# Moof_Janibore.net
KiCad netlist of a schematic drawn in EAGLE
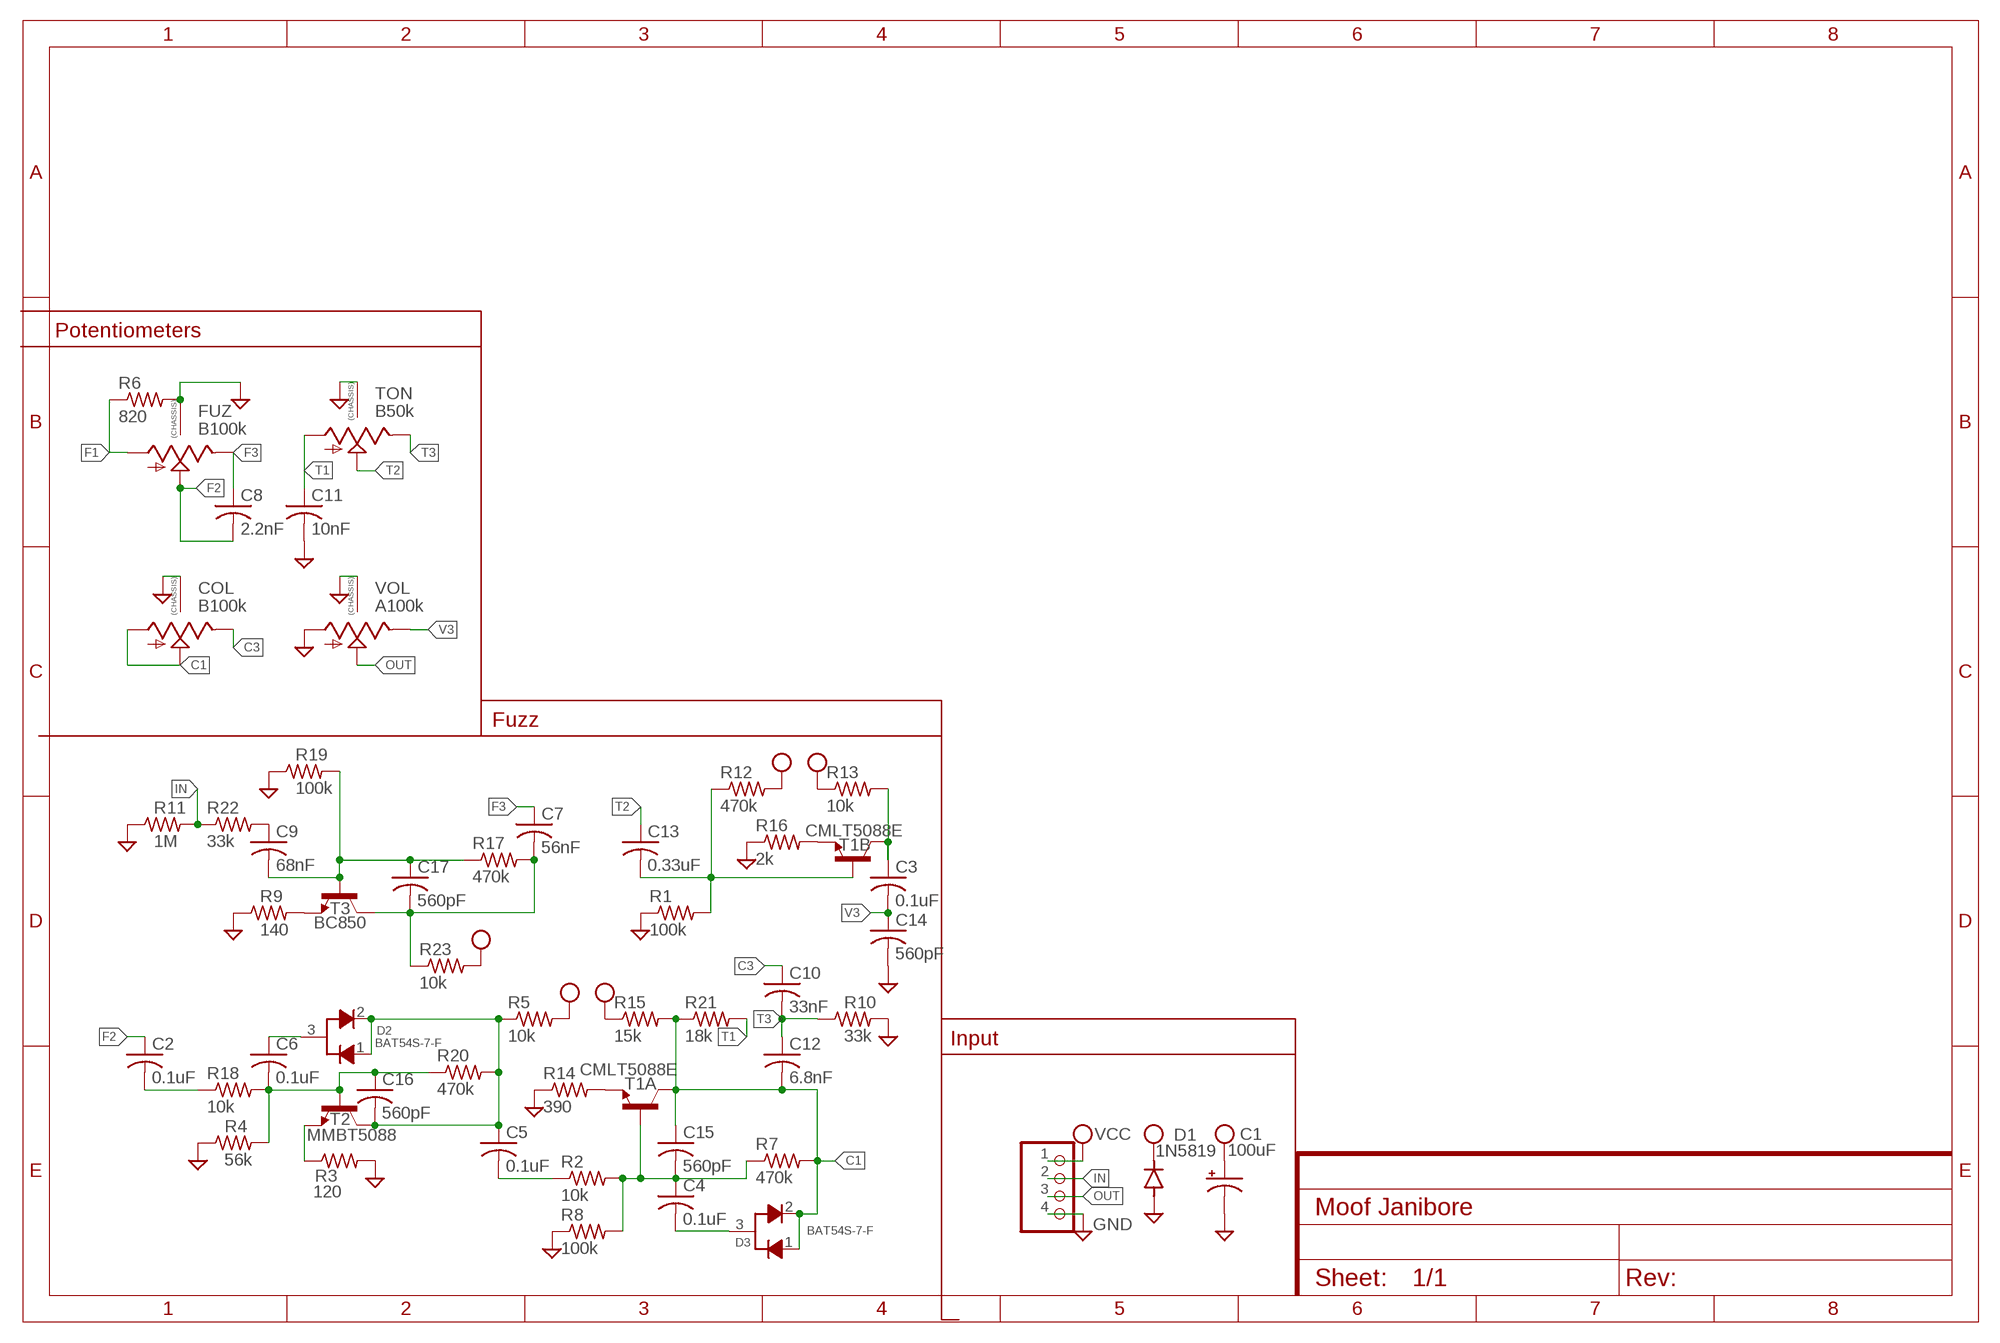
[diagram p0: schematic, sheet 1]

(export (version "E")
  (design (tool "Eeschema 10.0.6"))
  (components
    (comp (ref "C1")
      (value "100uF")
      (footprint "eagle-import:PAN_B_SMD+THRU")
      (libsource (lib "eagle-import") (part "CAP_SMD+THRUPAN_B"))
    )
    (comp (ref "C2")
      (value "0.1uF")
      (footprint "eagle-import:C0402")
      (libsource (lib "eagle-import") (part "C-USC0402"))
    )
    (comp (ref "C3")
      (value "0.1uF")
      (footprint "eagle-import:C0402")
      (libsource (lib "eagle-import") (part "C-USC0402"))
    )
    (comp (ref "C4")
      (value "0.1uF")
      (footprint "eagle-import:C0402")
      (libsource (lib "eagle-import") (part "C-USC0402"))
    )
    (comp (ref "C5")
      (value "0.1uF")
      (footprint "eagle-import:C0402")
      (libsource (lib "eagle-import") (part "C-USC0402"))
    )
    (comp (ref "C6")
      (value "0.1uF")
      (footprint "eagle-import:C0402")
      (libsource (lib "eagle-import") (part "C-USC0402"))
    )
    (comp (ref "C7")
      (value "56nF")
      (footprint "eagle-import:C0402")
      (libsource (lib "eagle-import") (part "C-USC0402"))
    )
    (comp (ref "C8")
      (value "2.2nF")
      (footprint "eagle-import:C0402")
      (libsource (lib "eagle-import") (part "C-USC0402"))
    )
    (comp (ref "C9")
      (value "68nF")
      (footprint "eagle-import:C0402")
      (libsource (lib "eagle-import") (part "C-USC0402"))
    )
    (comp (ref "C10")
      (value "33nF")
      (footprint "eagle-import:C0402")
      (libsource (lib "eagle-import") (part "C-USC0402"))
    )
    (comp (ref "C11")
      (value "10nF")
      (footprint "eagle-import:C0402")
      (libsource (lib "eagle-import") (part "C-USC0402"))
    )
    (comp (ref "C12")
      (value "6.8nF")
      (footprint "eagle-import:C0402")
      (libsource (lib "eagle-import") (part "C-USC0402"))
    )
    (comp (ref "C13")
      (value "0.33uF")
      (footprint "eagle-import:C0402")
      (libsource (lib "eagle-import") (part "C-USC0402"))
    )
    (comp (ref "C14")
      (value "560pF")
      (footprint "eagle-import:C0402")
      (libsource (lib "eagle-import") (part "C-USC0402"))
    )
    (comp (ref "C15")
      (value "560pF")
      (footprint "eagle-import:C0402")
      (libsource (lib "eagle-import") (part "C-USC0402"))
    )
    (comp (ref "C16")
      (value "560pF")
      (footprint "eagle-import:C0402")
      (libsource (lib "eagle-import") (part "C-USC0402"))
    )
    (comp (ref "C17")
      (value "560pF")
      (footprint "eagle-import:C0402")
      (libsource (lib "eagle-import") (part "C-USC0402"))
    )
    (comp (ref "COL")
      (value "B100k")
      (footprint "eagle-import:9MM_SNAP-IN_POT")
      (libsource (lib "eagle-import") (part "9MM_SNAP-IN_POT_CHASSIS"))
    )
    (comp (ref "D1")
      (value "1N5819")
      (footprint "eagle-import:SOD123")
      (libsource (lib "eagle-import") (part "DIODE-SOD123"))
    )
    (comp (ref "D2")
      (value "BAT54S-7-F")
      (footprint "eagle-import:SOT23-3")
      (fields
        (field (name "DIGIKEY_PART_NUMBER") "BAT54S-FDITR-ND")
        (field (name "MANUFACTURER") "Diodes Incorporated")
        (field (name "CREATED_BY") "PCBLayout.com")
      )
      (libsource (lib "eagle-import") (part "BAT54S-7-F"))
    )
    (comp (ref "D3")
      (value "BAT54S-7-F")
      (footprint "eagle-import:SOT23-3")
      (fields
        (field (name "DIGIKEY_PART_NUMBER") "BAT54S-FDITR-ND")
        (field (name "MANUFACTURER") "Diodes Incorporated")
        (field (name "CREATED_BY") "PCBLayout.com")
      )
      (libsource (lib "eagle-import") (part "BAT54S-7-F"))
    )
    (comp (ref "FUZ")
      (value "B100k")
      (footprint "eagle-import:9MM_SNAP-IN_POT")
      (libsource (lib "eagle-import") (part "9MM_SNAP-IN_POT_CHASSIS"))
    )
    (comp (ref "JP1")
      (value "PINHD-1X4")
      (footprint "eagle-import:1X04")
      (libsource (lib "eagle-import") (part "PINHD-1X4"))
    )
    (comp (ref "R1")
      (value "100k")
      (footprint "eagle-import:R0402")
      (libsource (lib "eagle-import") (part "R-US_R0402"))
    )
    (comp (ref "R2")
      (value "10k")
      (footprint "eagle-import:R0402")
      (libsource (lib "eagle-import") (part "R-US_R0402"))
    )
    (comp (ref "R3")
      (value "120")
      (footprint "eagle-import:R0402")
      (libsource (lib "eagle-import") (part "R-US_R0402"))
    )
    (comp (ref "R4")
      (value "56k")
      (footprint "eagle-import:R0402")
      (libsource (lib "eagle-import") (part "R-US_R0402"))
    )
    (comp (ref "R5")
      (value "10k")
      (footprint "eagle-import:R0402")
      (libsource (lib "eagle-import") (part "R-US_R0402"))
    )
    (comp (ref "R6")
      (value "820")
      (footprint "eagle-import:R0402")
      (libsource (lib "eagle-import") (part "R-US_R0402"))
    )
    (comp (ref "R7")
      (value "470k")
      (footprint "eagle-import:R0402")
      (libsource (lib "eagle-import") (part "R-US_R0402"))
    )
    (comp (ref "R8")
      (value "100k")
      (footprint "eagle-import:R0402")
      (libsource (lib "eagle-import") (part "R-US_R0402"))
    )
    (comp (ref "R9")
      (value "140")
      (footprint "eagle-import:R0402")
      (libsource (lib "eagle-import") (part "R-US_R0402"))
    )
    (comp (ref "R10")
      (value "33k")
      (footprint "eagle-import:R0402")
      (libsource (lib "eagle-import") (part "R-US_R0402"))
    )
    (comp (ref "R11")
      (value "1M")
      (footprint "eagle-import:R0402")
      (libsource (lib "eagle-import") (part "R-US_R0402"))
    )
    (comp (ref "R12")
      (value "470k")
      (footprint "eagle-import:R0402")
      (libsource (lib "eagle-import") (part "R-US_R0402"))
    )
    (comp (ref "R13")
      (value "10k")
      (footprint "eagle-import:R0402")
      (libsource (lib "eagle-import") (part "R-US_R0402"))
    )
    (comp (ref "R14")
      (value "390")
      (footprint "eagle-import:R0402")
      (libsource (lib "eagle-import") (part "R-US_R0402"))
    )
    (comp (ref "R15")
      (value "15k")
      (footprint "eagle-import:R0402")
      (libsource (lib "eagle-import") (part "R-US_R0402"))
    )
    (comp (ref "R16")
      (value "2k")
      (footprint "eagle-import:R0402")
      (libsource (lib "eagle-import") (part "R-US_R0402"))
    )
    (comp (ref "R17")
      (value "470k")
      (footprint "eagle-import:R0402")
      (libsource (lib "eagle-import") (part "R-US_R0402"))
    )
    (comp (ref "R18")
      (value "10k")
      (footprint "eagle-import:R0402")
      (libsource (lib "eagle-import") (part "R-US_R0402"))
    )
    (comp (ref "R19")
      (value "100k")
      (footprint "eagle-import:R0402")
      (libsource (lib "eagle-import") (part "R-US_R0402"))
    )
    (comp (ref "R20")
      (value "470k")
      (footprint "eagle-import:R0402")
      (libsource (lib "eagle-import") (part "R-US_R0402"))
    )
    (comp (ref "R21")
      (value "18k")
      (footprint "eagle-import:R0402")
      (libsource (lib "eagle-import") (part "R-US_R0402"))
    )
    (comp (ref "R22")
      (value "33k")
      (footprint "eagle-import:R0402")
      (libsource (lib "eagle-import") (part "R-US_R0402"))
    )
    (comp (ref "R23")
      (value "10k")
      (footprint "eagle-import:R0402")
      (libsource (lib "eagle-import") (part "R-US_R0402"))
    )
    (comp (ref "T1")
      (value "CMLT5088E")
      (footprint "eagle-import:SOT563")
      (libsource (lib "eagle-import") (part "CMLT5088E"))
    )
    (comp (ref "T2")
      (value "MMBT5088")
      (footprint "eagle-import:SOT23-BEC")
      (libsource (lib "eagle-import") (part "-NPN-SOT23-BECBC850"))
    )
    (comp (ref "T3")
      (value "BC850")
      (footprint "eagle-import:SOT23-BEC")
      (libsource (lib "eagle-import") (part "-NPN-SOT23-BECBC850"))
    )
    (comp (ref "TON")
      (value "B50k")
      (footprint "eagle-import:9MM_SNAP-IN_POT")
      (libsource (lib "eagle-import") (part "9MM_SNAP-IN_POT_CHASSIS"))
    )
    (comp (ref "VOL")
      (value "A100k")
      (footprint "eagle-import:9MM_SNAP-IN_POT")
      (libsource (lib "eagle-import") (part "9MM_SNAP-IN_POT_CHASSIS"))
    )
  )
  (nets
    (net (code "1") (name "C1") (class "Default")
      (node (ref "C12") (pin "2") (pinfunction "2_2") (pintype "passive"))
      (node (ref "C15") (pin "1") (pinfunction "1_1") (pintype "passive"))
      (node (ref "COL") (pin "1") (pinfunction "A_1") (pintype "passive"))
      (node (ref "COL") (pin "2") (pinfunction "S_2") (pintype "passive"))
      (node (ref "D3") (pin "1") (pinfunction "1_1") (pintype "passive"))
      (node (ref "D3") (pin "2") (pinfunction "2_2") (pintype "passive"))
      (node (ref "R15") (pin "2") (pinfunction "2_2") (pintype "passive"))
      (node (ref "R21") (pin "1") (pinfunction "1_1") (pintype "passive"))
      (node (ref "R7") (pin "2") (pinfunction "2_2") (pintype "passive"))
      (node (ref "T1") (pin "6") (pinfunction "C_6") (pintype "passive"))
    )
    (net (code "2") (name "C3") (class "Default")
      (node (ref "C10") (pin "1") (pinfunction "1_1") (pintype "passive"))
      (node (ref "COL") (pin "3") (pinfunction "E_3") (pintype "passive"))
    )
    (net (code "3") (name "F1") (class "Default")
      (node (ref "FUZ") (pin "1") (pinfunction "A_1") (pintype "passive"))
      (node (ref "R6") (pin "1") (pinfunction "1_1") (pintype "passive"))
    )
    (net (code "4") (name "F2") (class "Default")
      (node (ref "C2") (pin "1") (pinfunction "1_1") (pintype "passive"))
      (node (ref "C8") (pin "2") (pinfunction "2_2") (pintype "passive"))
      (node (ref "FUZ") (pin "2") (pinfunction "S_2") (pintype "passive"))
    )
    (net (code "5") (name "F3") (class "Default")
      (node (ref "C7") (pin "1") (pinfunction "1_1") (pintype "passive"))
      (node (ref "C8") (pin "1") (pinfunction "1_1") (pintype "passive"))
      (node (ref "FUZ") (pin "3") (pinfunction "E_3") (pintype "passive"))
    )
    (net (code "6") (name "GND") (class "Default")
      (node (ref "C1") (pin "-") (pinfunction "-_-") (pintype "passive"))
      (node (ref "C1") (pin "--") (pinfunction "-_--") (pintype "passive"))
      (node (ref "C11") (pin "2") (pinfunction "2_2") (pintype "passive"))
      (node (ref "C14") (pin "2") (pinfunction "2_2") (pintype "passive"))
      (node (ref "COL") (pin "CHASSIS1") (pinfunction "P$1_CHASSIS1") (pintype "passive"))
      (node (ref "COL") (pin "CHASSIS2") (pinfunction "P$1_CHASSIS2") (pintype "passive"))
      (node (ref "D1") (pin "A") (pinfunction "A_A") (pintype "passive"))
      (node (ref "FUZ") (pin "CHASSIS1") (pinfunction "P$1_CHASSIS1") (pintype "passive"))
      (node (ref "FUZ") (pin "CHASSIS2") (pinfunction "P$1_CHASSIS2") (pintype "passive"))
      (node (ref "JP1") (pin "4") (pinfunction "4_4") (pintype "passive"))
      (node (ref "R1") (pin "1") (pinfunction "1_1") (pintype "passive"))
      (node (ref "R10") (pin "2") (pinfunction "2_2") (pintype "passive"))
      (node (ref "R11") (pin "1") (pinfunction "1_1") (pintype "passive"))
      (node (ref "R14") (pin "1") (pinfunction "1_1") (pintype "passive"))
      (node (ref "R16") (pin "1") (pinfunction "1_1") (pintype "passive"))
      (node (ref "R19") (pin "1") (pinfunction "1_1") (pintype "passive"))
      (node (ref "R3") (pin "2") (pinfunction "2_2") (pintype "passive"))
      (node (ref "R4") (pin "1") (pinfunction "1_1") (pintype "passive"))
      (node (ref "R6") (pin "2") (pinfunction "2_2") (pintype "passive"))
      (node (ref "R8") (pin "1") (pinfunction "1_1") (pintype "passive"))
      (node (ref "R9") (pin "1") (pinfunction "1_1") (pintype "passive"))
      (node (ref "TON") (pin "CHASSIS1") (pinfunction "P$1_CHASSIS1") (pintype "passive"))
      (node (ref "TON") (pin "CHASSIS2") (pinfunction "P$1_CHASSIS2") (pintype "passive"))
      (node (ref "VOL") (pin "1") (pinfunction "A_1") (pintype "passive"))
      (node (ref "VOL") (pin "CHASSIS1") (pinfunction "P$1_CHASSIS1") (pintype "passive"))
      (node (ref "VOL") (pin "CHASSIS2") (pinfunction "P$1_CHASSIS2") (pintype "passive"))
    )
    (net (code "7") (name "IN") (class "Default")
      (node (ref "JP1") (pin "2") (pinfunction "2_2") (pintype "passive"))
      (node (ref "R11") (pin "2") (pinfunction "2_2") (pintype "passive"))
      (node (ref "R22") (pin "1") (pinfunction "1_1") (pintype "passive"))
    )
    (net (code "8") (name "Net-(C2-Pad2)") (class "Default")
      (node (ref "C2") (pin "2") (pinfunction "2_2") (pintype "passive"))
      (node (ref "R18") (pin "1") (pinfunction "1_1") (pintype "passive"))
    )
    (net (code "9") (name "Net-(C4-Pad2)") (class "Default")
      (node (ref "C4") (pin "2") (pinfunction "2_2") (pintype "passive"))
      (node (ref "D3") (pin "3") (pinfunction "3_3") (pintype "passive"))
    )
    (net (code "10") (name "Net-(C5-Pad2)") (class "Default")
      (node (ref "C5") (pin "2") (pinfunction "2_2") (pintype "passive"))
      (node (ref "R2") (pin "1") (pinfunction "1_1") (pintype "passive"))
    )
    (net (code "11") (name "Net-(C6-Pad1)") (class "Default")
      (node (ref "C6") (pin "1") (pinfunction "1_1") (pintype "passive"))
      (node (ref "D2") (pin "3") (pinfunction "3_3") (pintype "passive"))
    )
    (net (code "12") (name "Net-(C9-Pad1)") (class "Default")
      (node (ref "C9") (pin "1") (pinfunction "1_1") (pintype "passive"))
      (node (ref "R22") (pin "2") (pinfunction "2_2") (pintype "passive"))
    )
    (net (code "13") (name "Net-(C16-Pad1)") (class "Default")
      (node (ref "C16") (pin "1") (pinfunction "1_1") (pintype "passive"))
      (node (ref "C6") (pin "2") (pinfunction "2_2") (pintype "passive"))
      (node (ref "R18") (pin "2") (pinfunction "2_2") (pintype "passive"))
      (node (ref "R20") (pin "1") (pinfunction "1_1") (pintype "passive"))
      (node (ref "R4") (pin "2") (pinfunction "2_2") (pintype "passive"))
      (node (ref "T2") (pin "B") (pinfunction "B_B") (pintype "passive"))
    )
    (net (code "14") (name "Net-(C16-Pad2)") (class "Default")
      (node (ref "C16") (pin "2") (pinfunction "2_2") (pintype "passive"))
      (node (ref "C5") (pin "1") (pinfunction "1_1") (pintype "passive"))
      (node (ref "D2") (pin "1") (pinfunction "1_1") (pintype "passive"))
      (node (ref "D2") (pin "2") (pinfunction "2_2") (pintype "passive"))
      (node (ref "R20") (pin "2") (pinfunction "2_2") (pintype "passive"))
      (node (ref "R5") (pin "1") (pinfunction "1_1") (pintype "passive"))
      (node (ref "T2") (pin "C") (pinfunction "C_C") (pintype "passive"))
    )
    (net (code "15") (name "Net-(C17-Pad1)") (class "Default")
      (node (ref "C17") (pin "1") (pinfunction "1_1") (pintype "passive"))
      (node (ref "C9") (pin "2") (pinfunction "2_2") (pintype "passive"))
      (node (ref "R17") (pin "1") (pinfunction "1_1") (pintype "passive"))
      (node (ref "R19") (pin "2") (pinfunction "2_2") (pintype "passive"))
      (node (ref "T3") (pin "B") (pinfunction "B_B") (pintype "passive"))
    )
    (net (code "16") (name "Net-(C17-Pad2)") (class "Default")
      (node (ref "C17") (pin "2") (pinfunction "2_2") (pintype "passive"))
      (node (ref "C7") (pin "2") (pinfunction "2_2") (pintype "passive"))
      (node (ref "R17") (pin "2") (pinfunction "2_2") (pintype "passive"))
      (node (ref "R23") (pin "1") (pinfunction "1_1") (pintype "passive"))
      (node (ref "T3") (pin "C") (pinfunction "C_C") (pintype "passive"))
    )
    (net (code "17") (name "Net-(R3-Pad1)") (class "Default")
      (node (ref "R3") (pin "1") (pinfunction "1_1") (pintype "passive"))
      (node (ref "T2") (pin "E") (pinfunction "E_E") (pintype "passive"))
    )
    (net (code "18") (name "Net-(R9-Pad2)") (class "Default")
      (node (ref "R9") (pin "2") (pinfunction "2_2") (pintype "passive"))
      (node (ref "T3") (pin "E") (pinfunction "E_E") (pintype "passive"))
    )
    (net (code "19") (name "Net-(T1A-B)") (class "Default")
      (node (ref "C15") (pin "2") (pinfunction "2_2") (pintype "passive"))
      (node (ref "C4") (pin "1") (pinfunction "1_1") (pintype "passive"))
      (node (ref "R2") (pin "2") (pinfunction "2_2") (pintype "passive"))
      (node (ref "R7") (pin "1") (pinfunction "1_1") (pintype "passive"))
      (node (ref "R8") (pin "2") (pinfunction "2_2") (pintype "passive"))
      (node (ref "T1") (pin "2") (pinfunction "B_2") (pintype "passive"))
    )
    (net (code "20") (name "Net-(T1A-E)") (class "Default")
      (node (ref "R14") (pin "2") (pinfunction "2_2") (pintype "passive"))
      (node (ref "T1") (pin "1") (pinfunction "E_1") (pintype "passive"))
    )
    (net (code "21") (name "Net-(T1B-B)") (class "Default")
      (node (ref "C13") (pin "2") (pinfunction "2_2") (pintype "passive"))
      (node (ref "R1") (pin "2") (pinfunction "2_2") (pintype "passive"))
      (node (ref "R12") (pin "1") (pinfunction "1_1") (pintype "passive"))
      (node (ref "T1") (pin "5") (pinfunction "B_5") (pintype "passive"))
    )
    (net (code "22") (name "Net-(T1B-C)") (class "Default")
      (node (ref "C3") (pin "1") (pinfunction "1_1") (pintype "passive"))
      (node (ref "R13") (pin "2") (pinfunction "2_2") (pintype "passive"))
      (node (ref "T1") (pin "3") (pinfunction "C_3") (pintype "passive"))
    )
    (net (code "23") (name "Net-(T1B-E)") (class "Default")
      (node (ref "R16") (pin "2") (pinfunction "2_2") (pintype "passive"))
      (node (ref "T1") (pin "4") (pinfunction "E_4") (pintype "passive"))
    )
    (net (code "24") (name "OUT") (class "Default")
      (node (ref "JP1") (pin "3") (pinfunction "3_3") (pintype "passive"))
      (node (ref "VOL") (pin "2") (pinfunction "S_2") (pintype "passive"))
    )
    (net (code "25") (name "T1") (class "Default")
      (node (ref "C11") (pin "1") (pinfunction "1_1") (pintype "passive"))
      (node (ref "R21") (pin "2") (pinfunction "2_2") (pintype "passive"))
      (node (ref "TON") (pin "1") (pinfunction "A_1") (pintype "passive"))
    )
    (net (code "26") (name "T2") (class "Default")
      (node (ref "C13") (pin "1") (pinfunction "1_1") (pintype "passive"))
      (node (ref "TON") (pin "2") (pinfunction "S_2") (pintype "passive"))
    )
    (net (code "27") (name "T3") (class "Default")
      (node (ref "C10") (pin "2") (pinfunction "2_2") (pintype "passive"))
      (node (ref "C12") (pin "1") (pinfunction "1_1") (pintype "passive"))
      (node (ref "R10") (pin "1") (pinfunction "1_1") (pintype "passive"))
      (node (ref "TON") (pin "3") (pinfunction "E_3") (pintype "passive"))
    )
    (net (code "28") (name "V3") (class "Default")
      (node (ref "C14") (pin "1") (pinfunction "1_1") (pintype "passive"))
      (node (ref "C3") (pin "2") (pinfunction "2_2") (pintype "passive"))
      (node (ref "VOL") (pin "3") (pinfunction "E_3") (pintype "passive"))
    )
    (net (code "29") (name "VCC") (class "Default")
      (node (ref "C1") (pin "+") (pinfunction "+_+") (pintype "passive"))
      (node (ref "C1") (pin "++") (pinfunction "+_++") (pintype "passive"))
      (node (ref "D1") (pin "C") (pinfunction "C_C") (pintype "passive"))
      (node (ref "JP1") (pin "1") (pinfunction "1_1") (pintype "passive"))
      (node (ref "R12") (pin "2") (pinfunction "2_2") (pintype "passive"))
      (node (ref "R13") (pin "1") (pinfunction "1_1") (pintype "passive"))
      (node (ref "R15") (pin "1") (pinfunction "1_1") (pintype "passive"))
      (node (ref "R23") (pin "2") (pinfunction "2_2") (pintype "passive"))
      (node (ref "R5") (pin "2") (pinfunction "2_2") (pintype "passive"))
    )
  )
)
